# Clock_Led7_23.net
KiCad netlist of a schematic drawn in Altium Designer
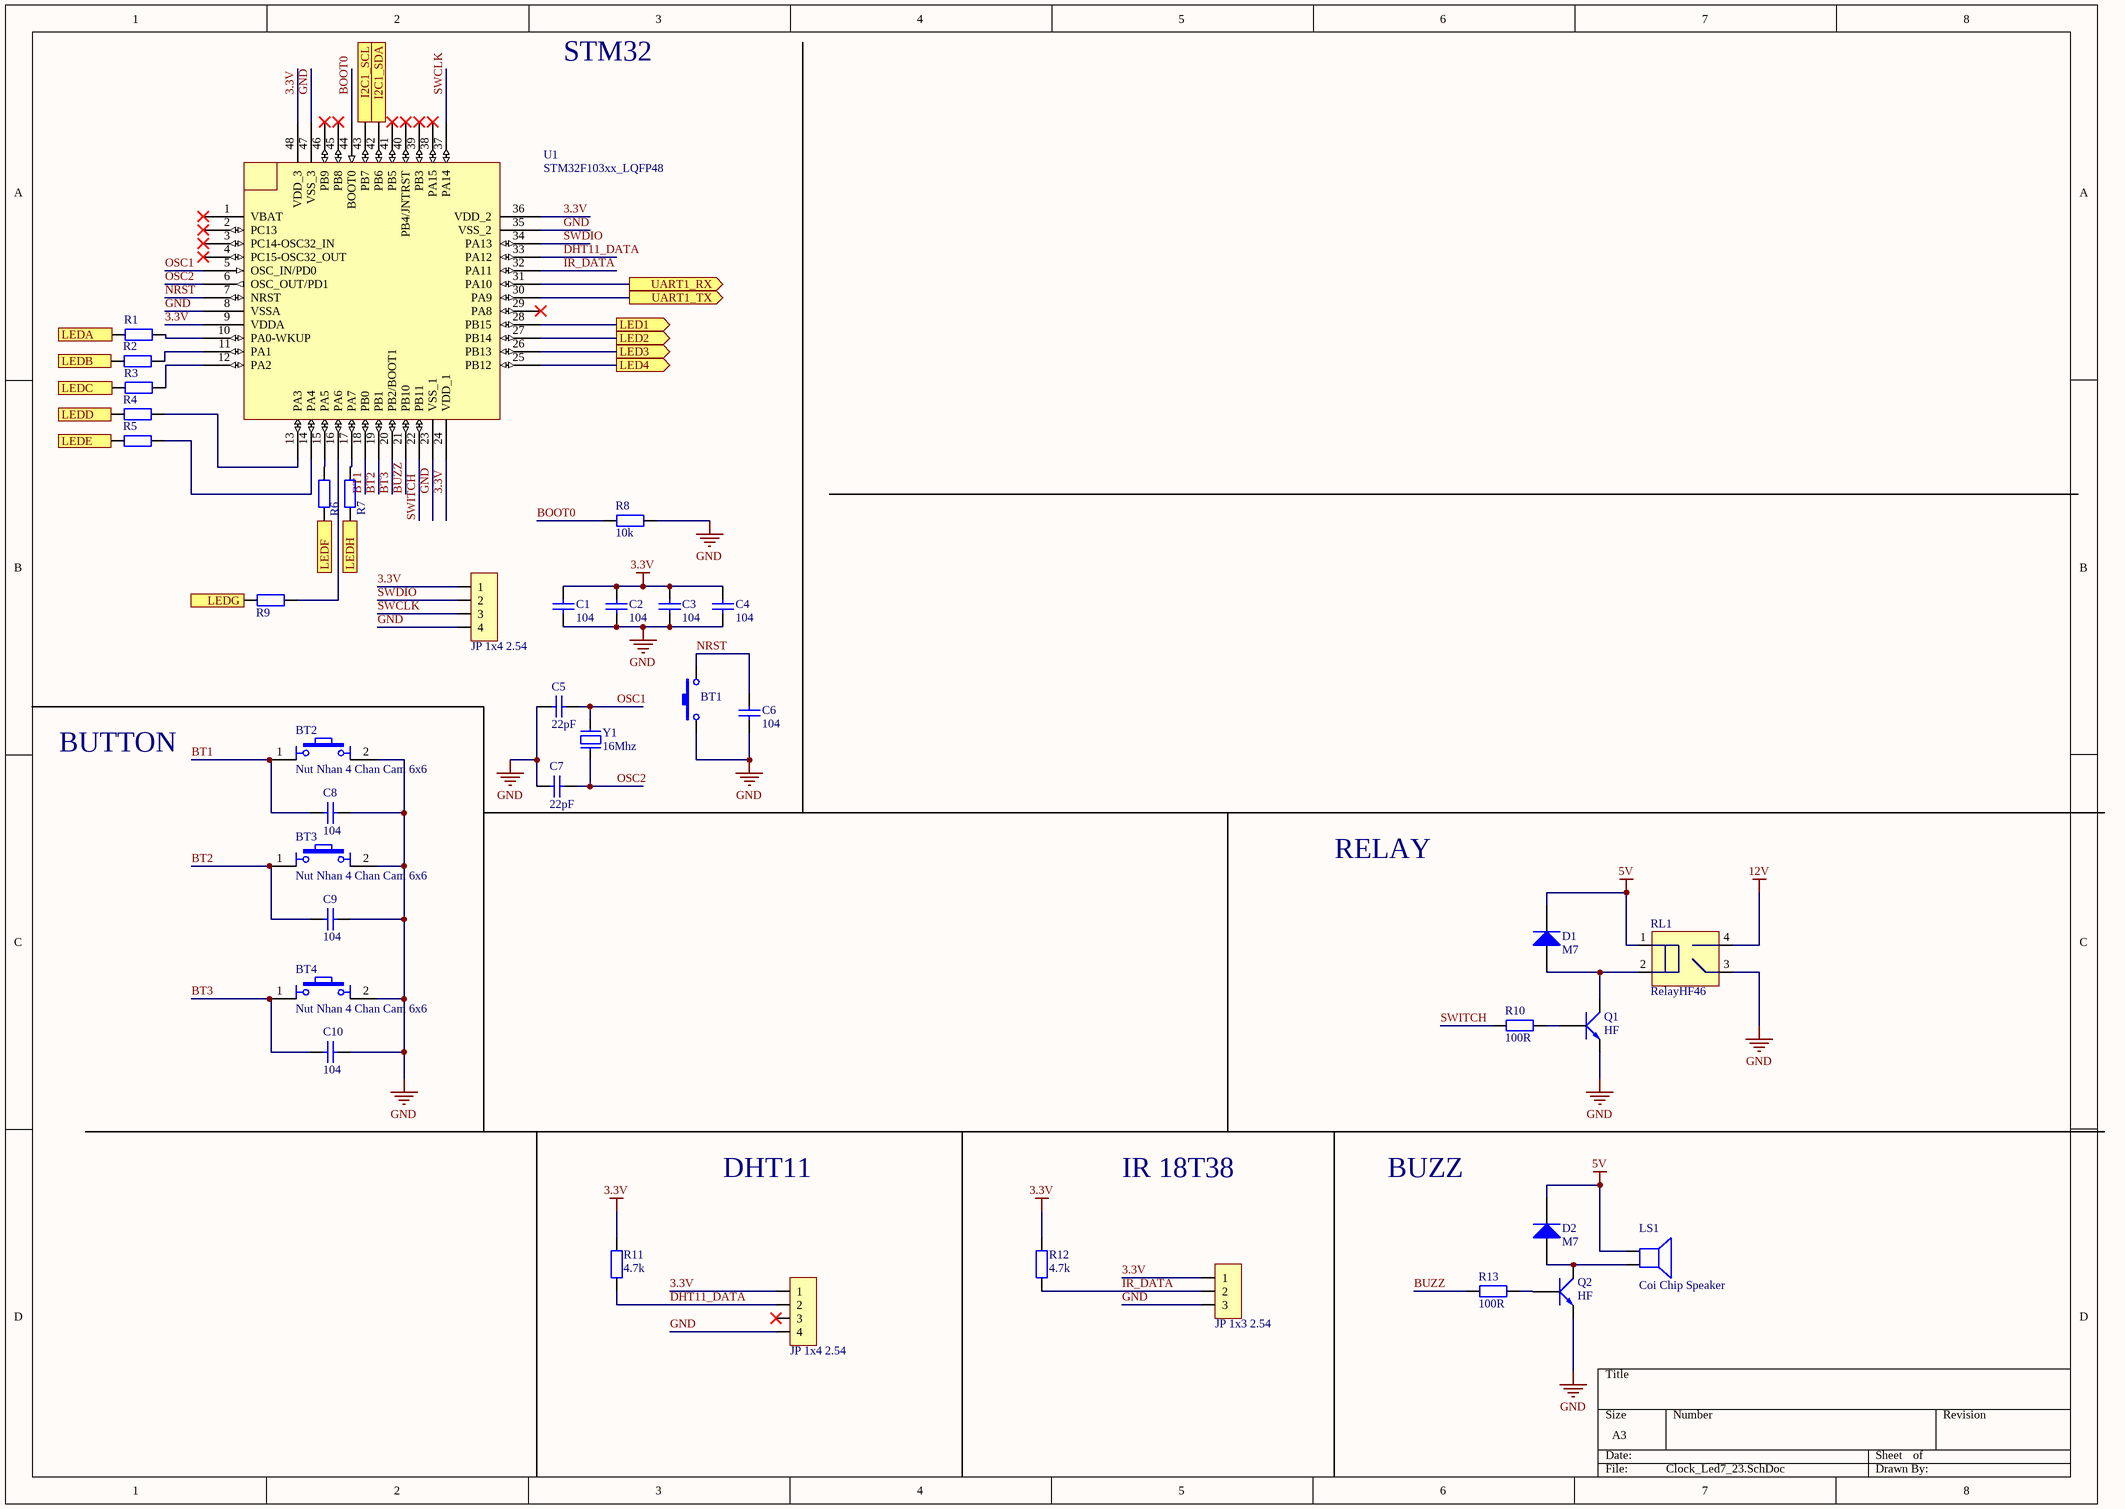
[diagram p0: Clock_Led7_23.SchDoc]

(export (version "E")
  (design (tool "Eeschema 10.0.6"))
  (components
    (comp (ref "BT1")
      (value "Nut Nhan 2 Chan SMD 3x6x2.5")
      (footprint "Nut Nhan 2 Chan SMD 3x6x2.5")
      (libsource (lib "Altium_Lib_by_KhueNguyenCreator") (part "Nut Nhan 2 Chan SMD 3x6x2.5"))
    )
    (comp (ref "BT2")
      (value "Nut Nhan 4 Chan Cam 6x6")
      (footprint "Nut Nhan 4 Chan Cam 6x6")
      (description "Nut Nhan 4 Chan 6x6mm")
      (libsource (lib "Altium_Lib_by_KhueNguyenCreator") (part "Nut Nhan 4 Chan Cam 6x6"))
    )
    (comp (ref "BT3")
      (value "Nut Nhan 4 Chan Cam 6x6")
      (footprint "Nut Nhan 4 Chan Cam 6x6")
      (description "Nut Nhan 4 Chan 6x6mm")
      (libsource (lib "Altium_Lib_by_KhueNguyenCreator") (part "Nut Nhan 4 Chan Cam 6x6"))
    )
    (comp (ref "BT4")
      (value "Nut Nhan 4 Chan Cam 6x6")
      (footprint "Nut Nhan 4 Chan Cam 6x6")
      (description "Nut Nhan 4 Chan 6x6mm")
      (libsource (lib "Altium_Lib_by_KhueNguyenCreator") (part "Nut Nhan 4 Chan Cam 6x6"))
    )
    (comp (ref "C1")
      (value "104")
      (footprint "tu 0805")
      (description "Dán")
      (libsource (lib "Altium_Lib_by_KhueNguyenCreator") (part "Tu 0805 104 50V 10%"))
    )
    (comp (ref "C2")
      (value "104")
      (footprint "tu 0805")
      (description "Dán")
      (libsource (lib "Altium_Lib_by_KhueNguyenCreator") (part "Tu 0805 104 50V 10%"))
    )
    (comp (ref "C3")
      (value "104")
      (footprint "tu 0805")
      (description "Dán")
      (libsource (lib "Altium_Lib_by_KhueNguyenCreator") (part "Tu 0805 104 50V 10%"))
    )
    (comp (ref "C4")
      (value "104")
      (footprint "tu 0805")
      (description "Dán")
      (libsource (lib "Altium_Lib_by_KhueNguyenCreator") (part "Tu 0805 104 50V 10%"))
    )
    (comp (ref "C5")
      (value "22pF")
      (footprint "tu 0805")
      (description "Dán")
      (libsource (lib "Altium_Lib_by_KhueNguyenCreator") (part "Tu 0805 22pF 50V 10%"))
    )
    (comp (ref "C6")
      (value "104")
      (footprint "tu 0805")
      (description "Dán")
      (libsource (lib "Altium_Lib_by_KhueNguyenCreator") (part "Tu 0805 104 50V 10%"))
    )
    (comp (ref "C7")
      (value "22pF")
      (footprint "tu 0805")
      (description "Dán")
      (libsource (lib "Altium_Lib_by_KhueNguyenCreator") (part "Tu 0805 22pF 50V 10%"))
    )
    (comp (ref "C8")
      (value "104")
      (footprint "tu 0805")
      (description "Dán")
      (libsource (lib "Altium_Lib_by_KhueNguyenCreator") (part "Tu 0805 104 50V 10%"))
    )
    (comp (ref "C9")
      (value "104")
      (footprint "tu 0805")
      (description "Dán")
      (libsource (lib "Altium_Lib_by_KhueNguyenCreator") (part "Tu 0805 104 50V 10%"))
    )
    (comp (ref "C10")
      (value "104")
      (footprint "tu 0805")
      (description "Dán")
      (libsource (lib "Altium_Lib_by_KhueNguyenCreator") (part "Tu 0805 104 50V 10%"))
    )
    (comp (ref "D1")
      (value "M7")
      (footprint "DIODE SMA")
      (description "Dán")
      (libsource (lib "Altium_Lib_by_KhueNguyenCreator") (part "Diode M7 ( 4007 )"))
    )
    (comp (ref "D2")
      (value "M7")
      (footprint "DIODE SMA")
      (description "Dán")
      (libsource (lib "Altium_Lib_by_KhueNguyenCreator") (part "Diode M7 ( 4007 )"))
    )
    (comp (ref "JP1")
      (value "JP 1x4 2.54")
      (footprint "JP 1x4 DT")
      (description "Cắm")
      (libsource (lib "Altium_Lib_by_KhueNguyenCreator") (part "JP 1x4 2.54 Duc Thang"))
    )
    (comp (ref "JP2")
      (value "JP 1x3 2.54")
      (footprint "JP 1x3 CT")
      (description "Cắm")
      (libsource (lib "Altium_Lib_by_KhueNguyenCreator") (part "JP 1x3 2.54 Cai Thang"))
    )
    (comp (ref "JP3")
      (value "JP 1x4 2.54")
      (footprint "JP 1x4 CT")
      (description "Cắm")
      (libsource (lib "Altium_Lib_by_KhueNguyenCreator") (part "JP 1x4 2.54 Cai Thang"))
    )
    (comp (ref "LS1")
      (value "Coi Chip Speaker")
      (footprint "Coi Chip Speacker")
      (description "Còi chip")
      (libsource (lib "Altium_Lib_by_KhueNguyenCreator") (part "Coi Chip Speaker"))
    )
    (comp (ref "Q1")
      (value "HF")
      (footprint "SOT23")
      (description "NPN transistor")
      (libsource (lib "Altium_Lib_by_KhueNguyenCreator") (part "C1815 HF SMD"))
    )
    (comp (ref "Q2")
      (value "HF")
      (footprint "SOT23")
      (description "NPN transistor")
      (libsource (lib "Altium_Lib_by_KhueNguyenCreator") (part "C1815 HF SMD"))
    )
    (comp (ref "R1")
      (value "100R")
      (footprint "tro smd 0805")
      (description "Dán")
      (libsource (lib "Altium_Lib_by_KhueNguyenCreator") (part "Tro 0805 5% 100R"))
    )
    (comp (ref "R2")
      (value "100R")
      (footprint "tro smd 0805")
      (description "Dán")
      (libsource (lib "Altium_Lib_by_KhueNguyenCreator") (part "Tro 0805 5% 100R"))
    )
    (comp (ref "R3")
      (value "100R")
      (footprint "tro smd 0805")
      (description "Dán")
      (libsource (lib "Altium_Lib_by_KhueNguyenCreator") (part "Tro 0805 5% 100R"))
    )
    (comp (ref "R4")
      (value "100R")
      (footprint "tro smd 0805")
      (description "Dán")
      (libsource (lib "Altium_Lib_by_KhueNguyenCreator") (part "Tro 0805 5% 100R"))
    )
    (comp (ref "R5")
      (value "100R")
      (footprint "tro smd 0805")
      (description "Dán")
      (libsource (lib "Altium_Lib_by_KhueNguyenCreator") (part "Tro 0805 5% 100R"))
    )
    (comp (ref "R6")
      (value "100R")
      (footprint "tro smd 0805")
      (description "Dán")
      (libsource (lib "Altium_Lib_by_KhueNguyenCreator") (part "Tro 0805 5% 100R"))
    )
    (comp (ref "R7")
      (value "100R")
      (footprint "tro smd 0805")
      (description "Dán")
      (libsource (lib "Altium_Lib_by_KhueNguyenCreator") (part "Tro 0805 5% 100R"))
    )
    (comp (ref "R8")
      (value "10k")
      (footprint "tro smd 0805")
      (description "Dán")
      (libsource (lib "Altium_Lib_by_KhueNguyenCreator") (part "Tro 0805 5% 10k"))
    )
    (comp (ref "R9")
      (value "100R")
      (footprint "tro smd 0805")
      (description "Dán")
      (libsource (lib "Altium_Lib_by_KhueNguyenCreator") (part "Tro 0805 5% 100R"))
    )
    (comp (ref "R10")
      (value "100R")
      (footprint "tro smd 0805")
      (description "Dán")
      (libsource (lib "Altium_Lib_by_KhueNguyenCreator") (part "Tro 0805 5% 100R"))
    )
    (comp (ref "R11")
      (value "4.7k")
      (footprint "tro smd 0805")
      (description "Dán")
      (libsource (lib "Altium_Lib_by_KhueNguyenCreator") (part "Tro 0805 5% 4.7k"))
    )
    (comp (ref "R12")
      (value "4.7k")
      (footprint "tro smd 0805")
      (description "Dán")
      (libsource (lib "Altium_Lib_by_KhueNguyenCreator") (part "Tro 0805 5% 4.7k"))
    )
    (comp (ref "R13")
      (value "100R")
      (footprint "tro smd 0805")
      (description "Dán")
      (libsource (lib "Altium_Lib_by_KhueNguyenCreator") (part "Tro 0805 5% 100R"))
    )
    (comp (ref "RL1")
      (value "RelayHF46")
      (footprint "Relay 4 chan HF46F")
      (description "Relay 4 chan HF46F")
      (libsource (lib "Altium_Lib_by_KhueNguyenCreator") (part "Relay 4 chan HF46F"))
    )
    (comp (ref "U1")
      (value "STM32F103xx_LQFP48")
      (footprint "STM32_LQPF48")
      (fields (field (name "PUBLISHER") "Altium Limited"))
      (libsource (lib "Altium_Lib_by_KhueNguyenCreator") (part "STM32F103xx_LQFP48"))
    )
    (comp (ref "Y1")
      (value "16Mhz")
      (footprint "Thach Anh 2 chan SMD")
      (description "Crystal For all Crystal 2pin.")
      (libsource (lib "Altium_Lib_by_KhueNguyenCreator") (part "Thach Anh 2 chan SMD"))
    )
  )
  (nets
    (net (code "1") (name "/BOOT0") (class "Default")
      (node (ref "R8") (pin "2") (pinfunction "2_2") (pintype "passive"))
      (node (ref "U1") (pin "44") (pinfunction "BOOT0_44") (pintype "input"))
    )
    (net (code "2") (name "/BT1") (class "Default")
      (node (ref "BT2") (pin "1") (pintype "passive"))
      (node (ref "C8") (pin "1") (pinfunction "1_1") (pintype "passive"))
      (node (ref "U1") (pin "18") (pinfunction "PB0_18") (pintype "bidirectional"))
    )
    (net (code "3") (name "/BT2") (class "Default")
      (node (ref "BT3") (pin "1") (pintype "passive"))
      (node (ref "C9") (pin "1") (pinfunction "1_1") (pintype "passive"))
      (node (ref "U1") (pin "19") (pinfunction "PB1_19") (pintype "bidirectional"))
    )
    (net (code "4") (name "/BT3") (class "Default")
      (node (ref "BT4") (pin "1") (pintype "passive"))
      (node (ref "C10") (pin "1") (pinfunction "1_1") (pintype "passive"))
      (node (ref "U1") (pin "20") (pinfunction "PB2/BOOT1_20") (pintype "bidirectional"))
    )
    (net (code "5") (name "/BUZZ") (class "Default")
      (node (ref "R13") (pin "1") (pinfunction "1_1") (pintype "passive"))
      (node (ref "U1") (pin "21") (pinfunction "PB10_21") (pintype "bidirectional"))
    )
    (net (code "6") (name "/DHT11_DATA") (class "Default")
      (node (ref "JP3") (pin "2") (pinfunction "2_2") (pintype "passive"))
      (node (ref "R11") (pin "1") (pinfunction "1_1") (pintype "passive"))
      (node (ref "U1") (pin "33") (pinfunction "PA12_33") (pintype "bidirectional"))
    )
    (net (code "7") (name "/I2C1_SCL") (class "Default")
      (node (ref "U1") (pin "43") (pinfunction "PB7_43") (pintype "bidirectional"))
    )
    (net (code "8") (name "/I2C1_SDA") (class "Default")
      (node (ref "U1") (pin "42") (pinfunction "PB6_42") (pintype "bidirectional"))
    )
    (net (code "9") (name "/IR_DATA") (class "Default")
      (node (ref "JP2") (pin "2") (pinfunction "2_2") (pintype "passive"))
      (node (ref "R12") (pin "1") (pinfunction "1_1") (pintype "passive"))
      (node (ref "U1") (pin "32") (pinfunction "PA11_32") (pintype "bidirectional"))
    )
    (net (code "10") (name "/LED1") (class "Default")
      (node (ref "U1") (pin "28") (pinfunction "PB15_28") (pintype "bidirectional"))
    )
    (net (code "11") (name "/LED2") (class "Default")
      (node (ref "U1") (pin "27") (pinfunction "PB14_27") (pintype "bidirectional"))
    )
    (net (code "12") (name "/LED3") (class "Default")
      (node (ref "U1") (pin "26") (pinfunction "PB13_26") (pintype "bidirectional"))
    )
    (net (code "13") (name "/LED4") (class "Default")
      (node (ref "U1") (pin "25") (pinfunction "PB12_25") (pintype "bidirectional"))
    )
    (net (code "14") (name "/LEDA") (class "Default")
      (node (ref "R1") (pin "1") (pinfunction "1_1") (pintype "passive"))
    )
    (net (code "15") (name "/LEDB") (class "Default")
      (node (ref "R2") (pin "1") (pinfunction "1_1") (pintype "passive"))
    )
    (net (code "16") (name "/LEDC") (class "Default")
      (node (ref "R3") (pin "1") (pinfunction "1_1") (pintype "passive"))
    )
    (net (code "17") (name "/LEDD") (class "Default")
      (node (ref "R4") (pin "1") (pinfunction "1_1") (pintype "passive"))
    )
    (net (code "18") (name "/LEDE") (class "Default")
      (node (ref "R5") (pin "1") (pinfunction "1_1") (pintype "passive"))
    )
    (net (code "19") (name "/LEDF") (class "Default")
      (node (ref "R6") (pin "1") (pinfunction "1_1") (pintype "passive"))
    )
    (net (code "20") (name "/LEDG") (class "Default")
      (node (ref "R9") (pin "2") (pinfunction "2_2") (pintype "passive"))
    )
    (net (code "21") (name "/LEDH") (class "Default")
      (node (ref "R7") (pin "1") (pinfunction "1_1") (pintype "passive"))
    )
    (net (code "22") (name "/NRST") (class "Default")
      (node (ref "BT1") (pin "2") (pinfunction "2_2") (pintype "passive"))
      (node (ref "C6") (pin "1") (pinfunction "1_1") (pintype "passive"))
      (node (ref "U1") (pin "7") (pinfunction "NRST_7") (pintype "bidirectional"))
    )
    (net (code "23") (name "/OSC1") (class "Default")
      (node (ref "C5") (pin "1") (pinfunction "1_1") (pintype "passive"))
      (node (ref "U1") (pin "5") (pinfunction "OSC_IN/PD0_5") (pintype "input"))
      (node (ref "Y1") (pin "2") (pinfunction "2_2") (pintype "passive"))
    )
    (net (code "24") (name "/OSC2") (class "Default")
      (node (ref "C7") (pin "2") (pinfunction "2_2") (pintype "passive"))
      (node (ref "U1") (pin "6") (pinfunction "OSC_OUT/PD1_6") (pintype "output"))
      (node (ref "Y1") (pin "1") (pinfunction "1_1") (pintype "passive"))
    )
    (net (code "25") (name "/SWCLK") (class "Default")
      (node (ref "JP1") (pin "3") (pinfunction "3_3") (pintype "passive"))
      (node (ref "U1") (pin "37") (pinfunction "PA14_37") (pintype "bidirectional"))
    )
    (net (code "26") (name "/SWDIO") (class "Default")
      (node (ref "JP1") (pin "2") (pinfunction "2_2") (pintype "passive"))
      (node (ref "U1") (pin "34") (pinfunction "PA13_34") (pintype "bidirectional"))
    )
    (net (code "27") (name "/SWITCH") (class "Default")
      (node (ref "R10") (pin "1") (pinfunction "1_1") (pintype "passive"))
      (node (ref "U1") (pin "22") (pinfunction "PB11_22") (pintype "bidirectional"))
    )
    (net (code "28") (name "/UART1_RX") (class "Default")
      (node (ref "U1") (pin "31") (pinfunction "PA10_31") (pintype "bidirectional"))
    )
    (net (code "29") (name "/UART1_TX") (class "Default")
      (node (ref "U1") (pin "30") (pinfunction "PA9_30") (pintype "bidirectional"))
    )
    (net (code "30") (name "3.3V") (class "Default")
      (node (ref "C1") (pin "1") (pinfunction "1_1") (pintype "passive"))
      (node (ref "C2") (pin "1") (pinfunction "1_1") (pintype "passive"))
      (node (ref "C3") (pin "1") (pinfunction "1_1") (pintype "passive"))
      (node (ref "C4") (pin "1") (pinfunction "1_1") (pintype "passive"))
      (node (ref "JP1") (pin "1") (pinfunction "1_1") (pintype "passive"))
      (node (ref "JP2") (pin "1") (pinfunction "1_1") (pintype "passive"))
      (node (ref "JP3") (pin "1") (pinfunction "1_1") (pintype "passive"))
      (node (ref "R11") (pin "2") (pinfunction "2_2") (pintype "passive"))
      (node (ref "R12") (pin "2") (pinfunction "2_2") (pintype "passive"))
      (node (ref "U1") (pin "24") (pinfunction "VDD_1_24") (pintype "power_in"))
      (node (ref "U1") (pin "36") (pinfunction "VDD_2_36") (pintype "power_in"))
      (node (ref "U1") (pin "48") (pinfunction "VDD_3_48") (pintype "power_in"))
      (node (ref "U1") (pin "9") (pinfunction "VDDA_9") (pintype "power_in"))
    )
    (net (code "31") (name "5V") (class "Default")
      (node (ref "D1") (pin "2") (pinfunction "K_2") (pintype "passive"))
      (node (ref "D2") (pin "2") (pinfunction "K_2") (pintype "passive"))
      (node (ref "LS1") (pin "1") (pinfunction "1_1") (pintype "passive"))
      (node (ref "RL1") (pin "1") (pintype "passive"))
    )
    (net (code "32") (name "12V") (class "Default")
      (node (ref "RL1") (pin "4") (pinfunction "AC/DC_4") (pintype "passive"))
    )
    (net (code "33") (name "GND") (class "Default")
      (node (ref "BT1") (pin "1") (pinfunction "1_1") (pintype "passive"))
      (node (ref "BT2") (pin "2") (pintype "passive"))
      (node (ref "BT3") (pin "2") (pintype "passive"))
      (node (ref "BT4") (pin "2") (pintype "passive"))
      (node (ref "C1") (pin "2") (pinfunction "2_2") (pintype "passive"))
      (node (ref "C10") (pin "2") (pinfunction "2_2") (pintype "passive"))
      (node (ref "C2") (pin "2") (pinfunction "2_2") (pintype "passive"))
      (node (ref "C3") (pin "2") (pinfunction "2_2") (pintype "passive"))
      (node (ref "C4") (pin "2") (pinfunction "2_2") (pintype "passive"))
      (node (ref "C5") (pin "2") (pinfunction "2_2") (pintype "passive"))
      (node (ref "C6") (pin "2") (pinfunction "2_2") (pintype "passive"))
      (node (ref "C7") (pin "1") (pinfunction "1_1") (pintype "passive"))
      (node (ref "C8") (pin "2") (pinfunction "2_2") (pintype "passive"))
      (node (ref "C9") (pin "2") (pinfunction "2_2") (pintype "passive"))
      (node (ref "JP1") (pin "4") (pinfunction "4_4") (pintype "passive"))
      (node (ref "JP2") (pin "3") (pinfunction "3_3") (pintype "passive"))
      (node (ref "JP3") (pin "4") (pinfunction "4_4") (pintype "passive"))
      (node (ref "Q1") (pin "2") (pinfunction "E_2") (pintype "passive"))
      (node (ref "Q2") (pin "2") (pinfunction "E_2") (pintype "passive"))
      (node (ref "R8") (pin "1") (pinfunction "1_1") (pintype "passive"))
      (node (ref "RL1") (pin "3") (pinfunction "AC/DC_3") (pintype "passive"))
      (node (ref "U1") (pin "23") (pinfunction "VSS_1_23") (pintype "power_in"))
      (node (ref "U1") (pin "35") (pinfunction "VSS_2_35") (pintype "power_in"))
      (node (ref "U1") (pin "47") (pinfunction "VSS_3_47") (pintype "power_in"))
      (node (ref "U1") (pin "8") (pinfunction "VSSA_8") (pintype "power_in"))
    )
    (net (code "34") (name "Net-(D1-A)") (class "Default")
      (node (ref "D1") (pin "1") (pinfunction "A_1") (pintype "passive"))
      (node (ref "Q1") (pin "3") (pinfunction "C_3") (pintype "passive"))
      (node (ref "RL1") (pin "2") (pintype "passive"))
    )
    (net (code "35") (name "Net-(D2-A)") (class "Default")
      (node (ref "D2") (pin "1") (pinfunction "A_1") (pintype "passive"))
      (node (ref "LS1") (pin "2") (pinfunction "2_2") (pintype "passive"))
      (node (ref "Q2") (pin "3") (pinfunction "C_3") (pintype "passive"))
    )
    (net (code "36") (name "Net-(Q1-B)") (class "Default")
      (node (ref "Q1") (pin "1") (pinfunction "B_1") (pintype "passive"))
      (node (ref "R10") (pin "2") (pinfunction "2_2") (pintype "passive"))
    )
    (net (code "37") (name "Net-(Q2-B)") (class "Default")
      (node (ref "Q2") (pin "1") (pinfunction "B_1") (pintype "passive"))
      (node (ref "R13") (pin "2") (pinfunction "2_2") (pintype "passive"))
    )
    (net (code "38") (name "Net-(U1-PA0-WKUP)") (class "Default")
      (node (ref "R1") (pin "2") (pinfunction "2_2") (pintype "passive"))
      (node (ref "U1") (pin "10") (pinfunction "PA0-WKUP_10") (pintype "bidirectional"))
    )
    (net (code "39") (name "Net-(U1-PA1)") (class "Default")
      (node (ref "R2") (pin "2") (pinfunction "2_2") (pintype "passive"))
      (node (ref "U1") (pin "11") (pinfunction "PA1_11") (pintype "bidirectional"))
    )
    (net (code "40") (name "Net-(U1-PA2)") (class "Default")
      (node (ref "R3") (pin "2") (pinfunction "2_2") (pintype "passive"))
      (node (ref "U1") (pin "12") (pinfunction "PA2_12") (pintype "bidirectional"))
    )
    (net (code "41") (name "Net-(U1-PA3)") (class "Default")
      (node (ref "R4") (pin "2") (pinfunction "2_2") (pintype "passive"))
      (node (ref "U1") (pin "13") (pinfunction "PA3_13") (pintype "bidirectional"))
    )
    (net (code "42") (name "Net-(U1-PA4)") (class "Default")
      (node (ref "R5") (pin "2") (pinfunction "2_2") (pintype "passive"))
      (node (ref "U1") (pin "14") (pinfunction "PA4_14") (pintype "bidirectional"))
    )
    (net (code "43") (name "Net-(U1-PA5)") (class "Default")
      (node (ref "R6") (pin "2") (pinfunction "2_2") (pintype "passive"))
      (node (ref "U1") (pin "15") (pinfunction "PA5_15") (pintype "bidirectional"))
    )
    (net (code "44") (name "Net-(U1-PA6)") (class "Default")
      (node (ref "R9") (pin "1") (pinfunction "1_1") (pintype "passive"))
      (node (ref "U1") (pin "16") (pinfunction "PA6_16") (pintype "bidirectional"))
    )
    (net (code "45") (name "Net-(U1-PA7)") (class "Default")
      (node (ref "R7") (pin "2") (pinfunction "2_2") (pintype "passive"))
      (node (ref "U1") (pin "17") (pinfunction "PA7_17") (pintype "bidirectional"))
    )
    (net (code "46") (name "unconnected-(JP3-Pad3)") (class "Default")
      (node (ref "JP3") (pin "3") (pinfunction "3_3") (pintype "passive+no_connect"))
    )
    (net (code "47") (name "unconnected-(U1-PA8-Pad29)") (class "Default")
      (node (ref "U1") (pin "29") (pinfunction "PA8_29") (pintype "bidirectional+no_connect"))
    )
    (net (code "48") (name "unconnected-(U1-PA15-Pad38)") (class "Default")
      (node (ref "U1") (pin "38") (pinfunction "PA15_38") (pintype "bidirectional+no_connect"))
    )
    (net (code "49") (name "unconnected-(U1-PB3-Pad39)") (class "Default")
      (node (ref "U1") (pin "39") (pinfunction "PB3_39") (pintype "bidirectional+no_connect"))
    )
    (net (code "50") (name "unconnected-(U1-PB4{slash}JNTRST-Pad40)") (class "Default")
      (node (ref "U1") (pin "40") (pinfunction "PB4/JNTRST_40") (pintype "bidirectional+no_connect"))
    )
    (net (code "51") (name "unconnected-(U1-PB5-Pad41)") (class "Default")
      (node (ref "U1") (pin "41") (pinfunction "PB5_41") (pintype "bidirectional+no_connect"))
    )
    (net (code "52") (name "unconnected-(U1-PB8-Pad45)") (class "Default")
      (node (ref "U1") (pin "45") (pinfunction "PB8_45") (pintype "bidirectional+no_connect"))
    )
    (net (code "53") (name "unconnected-(U1-PB9-Pad46)") (class "Default")
      (node (ref "U1") (pin "46") (pinfunction "PB9_46") (pintype "bidirectional+no_connect"))
    )
    (net (code "54") (name "unconnected-(U1-PC13-Pad2)") (class "Default")
      (node (ref "U1") (pin "2") (pinfunction "PC13_2") (pintype "bidirectional+no_connect"))
    )
    (net (code "55") (name "unconnected-(U1-PC14-OSC32_IN-Pad3)") (class "Default")
      (node (ref "U1") (pin "3") (pinfunction "PC14-OSC32_IN_3") (pintype "bidirectional+no_connect"))
    )
    (net (code "56") (name "unconnected-(U1-PC15-OSC32_OUT-Pad4)") (class "Default")
      (node (ref "U1") (pin "4") (pinfunction "PC15-OSC32_OUT_4") (pintype "bidirectional+no_connect"))
    )
    (net (code "57") (name "unconnected-(U1-VBAT-Pad1)") (class "Default")
      (node (ref "U1") (pin "1") (pinfunction "VBAT_1") (pintype "power_in+no_connect"))
    )
  )
)
